# Sheet1.net
KiCad netlist of a schematic drawn in Altium Designer
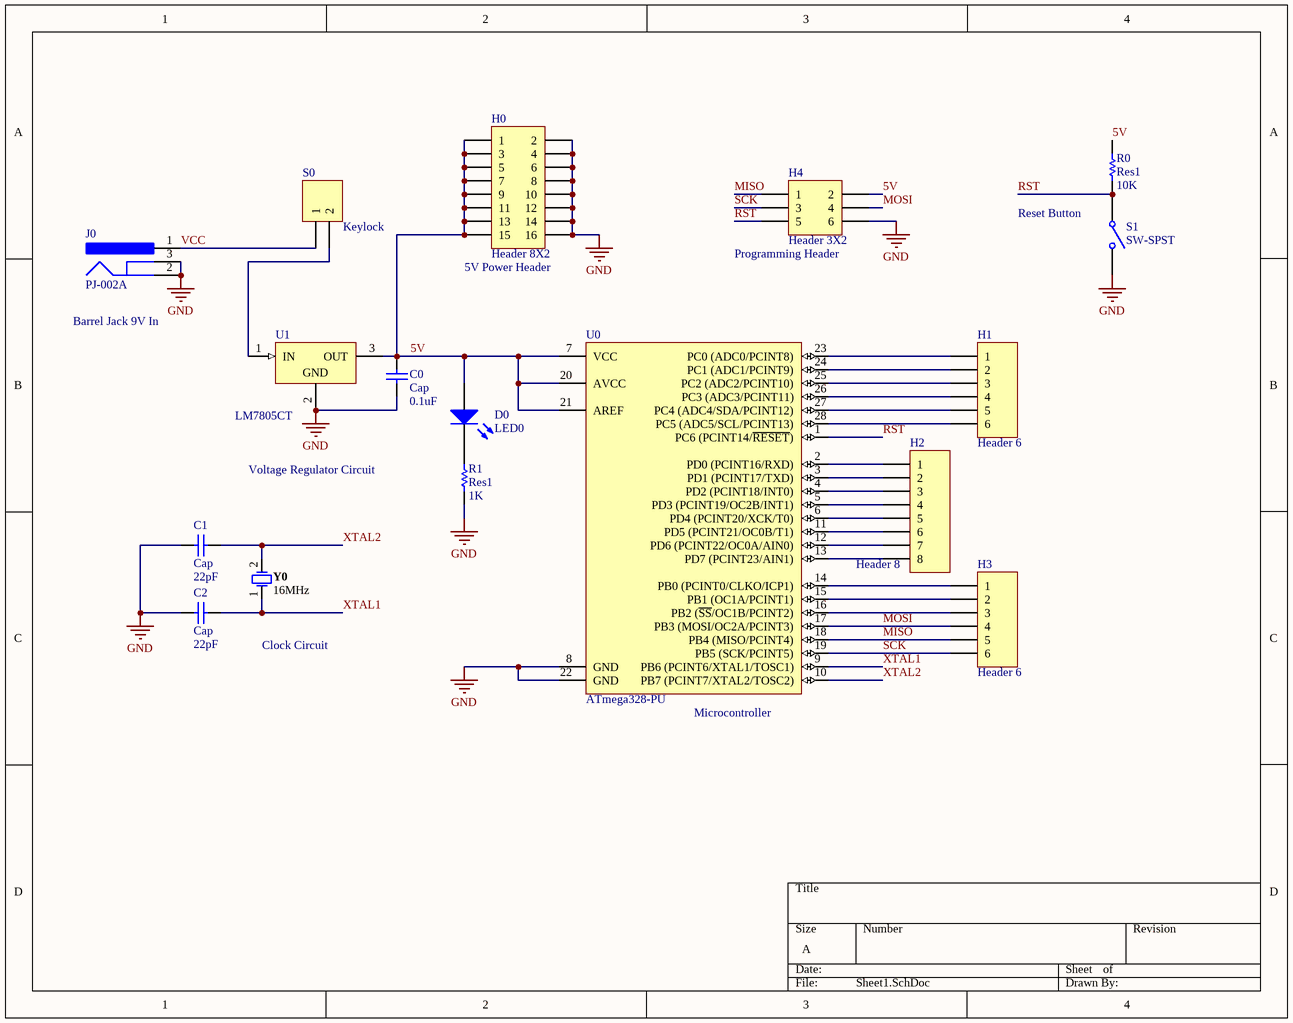
[diagram p0: Sheet1.SchDoc]

(export (version "E")
  (design (tool "Eeschema 10.0.6"))
  (components
    (comp (ref "C0")
      (value "Cap")
      (footprint "RAD-0.3")
      (description "Capacitor")
      (fields (field (name "ALTIUM_VALUE") "0.1uF") (field (name "PUBLISHER") "Altium Limited"))
      (libsource (lib "Miscellaneous Devices") (part "Cap"))
    )
    (comp (ref "C1")
      (value "Cap")
      (footprint "RAD-0.3")
      (description "Capacitor")
      (fields (field (name "ALTIUM_VALUE") "22pF") (field (name "PUBLISHER") "Altium Limited"))
      (libsource (lib "Miscellaneous Devices") (part "Cap"))
    )
    (comp (ref "C2")
      (value "Cap")
      (footprint "RAD-0.3")
      (description "Capacitor")
      (fields (field (name "ALTIUM_VALUE") "22pF") (field (name "PUBLISHER") "Altium Limited"))
      (libsource (lib "Miscellaneous Devices") (part "Cap"))
    )
    (comp (ref "D0")
      (value "LED0")
      (footprint "LED-0")
      (description "Typical INFRARED GaAs LED")
      (fields (field (name "PUBLISHER") "Altium Limited"))
      (libsource (lib "Miscellaneous Devices") (part "LED0"))
    )
    (comp (ref "H0")
      (value "Header 8X2")
      (footprint "HDR2X8")
      (description "Header, 8-Pin, Dual row")
      (fields (field (name "PUBLISHER") "Altium Limited"))
      (libsource (lib "Miscellaneous Connectors") (part "Header 8X2"))
    )
    (comp (ref "H1")
      (value "Header 6")
      (footprint "HDR1X6")
      (description "Header, 6-Pin")
      (fields (field (name "PUBLISHER") "Altium Limited"))
      (libsource (lib "Miscellaneous Connectors") (part "Header 6"))
    )
    (comp (ref "H2")
      (value "Header 8")
      (footprint "HDR1X8")
      (description "Header, 8-Pin")
      (fields (field (name "PUBLISHER") "Altium Limited"))
      (libsource (lib "Miscellaneous Connectors") (part "Header 8"))
    )
    (comp (ref "H3")
      (value "Header 6")
      (footprint "HDR1X6")
      (description "Header, 6-Pin")
      (fields (field (name "PUBLISHER") "Altium Limited"))
      (libsource (lib "Miscellaneous Connectors") (part "Header 6"))
    )
    (comp (ref "H4")
      (value "Header 3X2")
      (footprint "HDR2X3")
      (description "Header, 3-Pin, Dual row")
      (fields (field (name "PUBLISHER") "Altium Limited"))
      (libsource (lib "Miscellaneous Connectors") (part "Header 3X2"))
    )
    (comp (ref "J0")
      (value "PJ-002A")
      (footprint "CUI-PJ-002A_V")
      (fields (field (name "MANUFACTURER") "CUIInc."))
      (libsource (lib "Altium Content Vault") (part "JACK-2CD3-RN_B"))
    )
    (comp (ref "R0")
      (value "Res1")
      (footprint "AXIAL-0.5")
      (description "Resistor")
      (fields (field (name "ALTIUM_VALUE") "10K") (field (name "PUBLISHER") "Altium Limited"))
      (libsource (lib "Miscellaneous Devices") (part "Res1"))
    )
    (comp (ref "R1")
      (value "Res1")
      (footprint "AXIAL-0.5")
      (description "Resistor")
      (fields (field (name "ALTIUM_VALUE") "1K") (field (name "PUBLISHER") "Altium Limited"))
      (libsource (lib "Miscellaneous Devices") (part "Res1"))
    )
    (comp (ref "S0")
      (value "Keylock")
      (footprint "HDR1X2")
      (description "Header, 2-Pin")
      (fields (field (name "PUBLISHER") "Altium Limited"))
      (libsource (lib "Miscellaneous Connectors") (part "Header 2"))
    )
    (comp (ref "S1")
      (value "SW-SPST")
      (footprint "SPST-2")
      (description "Single-Pole, Single-Throw Switch")
      (fields (field (name "PUBLISHER") "Altium Limited"))
      (libsource (lib "Miscellaneous Devices") (part "SW-SPST"))
    )
    (comp (ref "U0")
      (value "ATmega328-PU")
      (footprint "28P3")
      (libsource (lib "Altium Content Vault") (part "MC-8B-ATM48-IL28"))
    )
    (comp (ref "U1")
      (value "LM7805CT")
      (footprint "FAIR-TO-220-3")
      (description "Positive Voltage Regulator, 5 V, 1 A, -40 to 125 degC, 3-Pin TO-220, RoHS, Tube")
      (fields (field (name "MANUFACTURER") "FairchildSemiconductor"))
      (libsource (lib "Altium Content Vault") (part "FAIR-LM7805CT-TO220-3"))
    )
    (comp (ref "Y0")
      (value "16MHz")
      (footprint "FOX-FOXSLF160-20")
      (description "Resistance Weld Thru-Hole Crystal, 16 MHz, -20 to 70 degC, 2-Pin THD, RoHS, Bulk")
      (fields (field (name "TOLERANCE") "1%"))
      (libsource (lib "Altium Content Vault") (part "XTAL-1-2-2"))
    )
  )
  (nets
    (net (code "1") (name "/5V") (class "Default")
      (node (ref "C0") (pin "2") (pinfunction "2_2") (pintype "passive"))
      (node (ref "D0") (pin "1") (pinfunction "A_1") (pintype "passive"))
      (node (ref "H0") (pin "1") (pinfunction "1_1") (pintype "passive"))
      (node (ref "H0") (pin "11") (pinfunction "11_11") (pintype "passive"))
      (node (ref "H0") (pin "13") (pinfunction "13_13") (pintype "passive"))
      (node (ref "H0") (pin "15") (pinfunction "15_15") (pintype "passive"))
      (node (ref "H0") (pin "3") (pinfunction "3_3") (pintype "passive"))
      (node (ref "H0") (pin "5") (pinfunction "5_5") (pintype "passive"))
      (node (ref "H0") (pin "7") (pinfunction "7_7") (pintype "passive"))
      (node (ref "H0") (pin "9") (pinfunction "9_9") (pintype "passive"))
      (node (ref "H4") (pin "2") (pinfunction "2_2") (pintype "passive"))
      (node (ref "R0") (pin "2") (pinfunction "2_2") (pintype "passive"))
      (node (ref "U0") (pin "20") (pinfunction "AVCC_20") (pintype "power_in"))
      (node (ref "U0") (pin "21") (pinfunction "AREF_21") (pintype "power_in"))
      (node (ref "U0") (pin "7") (pinfunction "VCC_7") (pintype "power_in"))
      (node (ref "U1") (pin "3") (pinfunction "OUT_3") (pintype "power_in"))
    )
    (net (code "2") (name "/MISO") (class "Default")
      (node (ref "H3") (pin "5") (pinfunction "5_5") (pintype "passive"))
      (node (ref "H4") (pin "1") (pinfunction "1_1") (pintype "passive"))
      (node (ref "U0") (pin "18") (pinfunction "PB4_(MISO/PCINT4)_18") (pintype "bidirectional"))
    )
    (net (code "3") (name "/MOSI") (class "Default")
      (node (ref "H3") (pin "4") (pinfunction "4_4") (pintype "passive"))
      (node (ref "H4") (pin "4") (pinfunction "4_4") (pintype "passive"))
      (node (ref "U0") (pin "17") (pinfunction "PB3_(MOSI/OC2A/PCINT3)_17") (pintype "bidirectional"))
    )
    (net (code "4") (name "/RST") (class "Default")
      (node (ref "H4") (pin "5") (pinfunction "5_5") (pintype "passive"))
      (node (ref "R0") (pin "1") (pinfunction "1_1") (pintype "passive"))
      (node (ref "S1") (pin "1") (pinfunction "COMMON_1") (pintype "passive"))
      (node (ref "U0") (pin "1") (pinfunction "PC6_(PCINT14/~{RESET})_1") (pintype "bidirectional"))
    )
    (net (code "5") (name "/SCK") (class "Default")
      (node (ref "H3") (pin "6") (pinfunction "6_6") (pintype "passive"))
      (node (ref "H4") (pin "3") (pinfunction "3_3") (pintype "passive"))
      (node (ref "U0") (pin "19") (pinfunction "PB5_(SCK/PCINT5)_19") (pintype "bidirectional"))
    )
    (net (code "6") (name "/VCC") (class "Default")
      (node (ref "J0") (pin "1") (pinfunction "1_1") (pintype "passive"))
      (node (ref "S0") (pin "1") (pinfunction "1_1") (pintype "passive"))
    )
    (net (code "7") (name "/XTAL1") (class "Default")
      (node (ref "C2") (pin "2") (pinfunction "2_2") (pintype "passive"))
      (node (ref "U0") (pin "9") (pinfunction "PB6_(PCINT6/XTAL1/TOSC1)_9") (pintype "bidirectional"))
      (node (ref "Y0") (pin "1") (pinfunction "1_1") (pintype "passive"))
    )
    (net (code "8") (name "/XTAL2") (class "Default")
      (node (ref "C1") (pin "2") (pinfunction "2_2") (pintype "passive"))
      (node (ref "U0") (pin "10") (pinfunction "PB7_(PCINT7/XTAL2/TOSC2)_10") (pintype "bidirectional"))
      (node (ref "Y0") (pin "2") (pinfunction "2_2") (pintype "passive"))
    )
    (net (code "9") (name "GND") (class "Default")
      (node (ref "C0") (pin "1") (pinfunction "1_1") (pintype "passive"))
      (node (ref "C1") (pin "1") (pinfunction "1_1") (pintype "passive"))
      (node (ref "C2") (pin "1") (pinfunction "1_1") (pintype "passive"))
      (node (ref "H0") (pin "10") (pinfunction "10_10") (pintype "passive"))
      (node (ref "H0") (pin "12") (pinfunction "12_12") (pintype "passive"))
      (node (ref "H0") (pin "14") (pinfunction "14_14") (pintype "passive"))
      (node (ref "H0") (pin "16") (pinfunction "16_16") (pintype "passive"))
      (node (ref "H0") (pin "2") (pinfunction "2_2") (pintype "passive"))
      (node (ref "H0") (pin "4") (pinfunction "4_4") (pintype "passive"))
      (node (ref "H0") (pin "6") (pinfunction "6_6") (pintype "passive"))
      (node (ref "H0") (pin "8") (pinfunction "8_8") (pintype "passive"))
      (node (ref "H4") (pin "6") (pinfunction "6_6") (pintype "passive"))
      (node (ref "J0") (pin "2") (pinfunction "2_2") (pintype "passive"))
      (node (ref "J0") (pin "3") (pinfunction "3_3") (pintype "passive"))
      (node (ref "R1") (pin "1") (pinfunction "1_1") (pintype "passive"))
      (node (ref "S1") (pin "2") (pinfunction "NO_2") (pintype "passive"))
      (node (ref "U0") (pin "22") (pinfunction "GND_22") (pintype "power_in"))
      (node (ref "U0") (pin "8") (pinfunction "GND_8") (pintype "power_in"))
      (node (ref "U1") (pin "2") (pinfunction "GND_2") (pintype "passive"))
    )
    (net (code "10") (name "Net-(D0-K)") (class "Default")
      (node (ref "D0") (pin "2") (pinfunction "K_2") (pintype "passive"))
      (node (ref "R1") (pin "2") (pinfunction "2_2") (pintype "passive"))
    )
    (net (code "11") (name "Net-(U0-PB0_(PCINT0{slash}CLKO{slash}ICP1))") (class "Default")
      (node (ref "H3") (pin "1") (pinfunction "1_1") (pintype "passive"))
      (node (ref "U0") (pin "14") (pinfunction "PB0_(PCINT0/CLKO/ICP1)_14") (pintype "bidirectional"))
    )
    (net (code "12") (name "Net-(U0-PB1_(OC1A{slash}PCINT1))") (class "Default")
      (node (ref "H3") (pin "2") (pinfunction "2_2") (pintype "passive"))
      (node (ref "U0") (pin "15") (pinfunction "PB1_(OC1A/PCINT1)_15") (pintype "bidirectional"))
    )
    (net (code "13") (name "Net-(U0-PB2_(~{SS}{slash}OC1B{slash}PCINT2))") (class "Default")
      (node (ref "H3") (pin "3") (pinfunction "3_3") (pintype "passive"))
      (node (ref "U0") (pin "16") (pinfunction "PB2_(~{SS}/OC1B/PCINT2)_16") (pintype "bidirectional"))
    )
    (net (code "14") (name "Net-(U0-PC0_(ADC0{slash}PCINT8))") (class "Default")
      (node (ref "H1") (pin "1") (pinfunction "1_1") (pintype "passive"))
      (node (ref "U0") (pin "23") (pinfunction "PC0_(ADC0/PCINT8)_23") (pintype "bidirectional"))
    )
    (net (code "15") (name "Net-(U0-PC1_(ADC1{slash}PCINT9))") (class "Default")
      (node (ref "H1") (pin "2") (pinfunction "2_2") (pintype "passive"))
      (node (ref "U0") (pin "24") (pinfunction "PC1_(ADC1/PCINT9)_24") (pintype "bidirectional"))
    )
    (net (code "16") (name "Net-(U0-PC2_(ADC2{slash}PCINT10))") (class "Default")
      (node (ref "H1") (pin "3") (pinfunction "3_3") (pintype "passive"))
      (node (ref "U0") (pin "25") (pinfunction "PC2_(ADC2/PCINT10)_25") (pintype "bidirectional"))
    )
    (net (code "17") (name "Net-(U0-PC3_(ADC3{slash}PCINT11))") (class "Default")
      (node (ref "H1") (pin "4") (pinfunction "4_4") (pintype "passive"))
      (node (ref "U0") (pin "26") (pinfunction "PC3_(ADC3/PCINT11)_26") (pintype "bidirectional"))
    )
    (net (code "18") (name "Net-(U0-PC4_(ADC4{slash}SDA{slash}PCINT12))") (class "Default")
      (node (ref "H1") (pin "5") (pinfunction "5_5") (pintype "passive"))
      (node (ref "U0") (pin "27") (pinfunction "PC4_(ADC4/SDA/PCINT12)_27") (pintype "bidirectional"))
    )
    (net (code "19") (name "Net-(U0-PC5_(ADC5{slash}SCL{slash}PCINT13))") (class "Default")
      (node (ref "H1") (pin "6") (pinfunction "6_6") (pintype "passive"))
      (node (ref "U0") (pin "28") (pinfunction "PC5_(ADC5/SCL/PCINT13)_28") (pintype "bidirectional"))
    )
    (net (code "20") (name "Net-(U0-PD0_(PCINT16{slash}RXD))") (class "Default")
      (node (ref "H2") (pin "1") (pinfunction "1_1") (pintype "passive"))
      (node (ref "U0") (pin "2") (pinfunction "PD0_(PCINT16/RXD)_2") (pintype "bidirectional"))
    )
    (net (code "21") (name "Net-(U0-PD1_(PCINT17{slash}TXD))") (class "Default")
      (node (ref "H2") (pin "2") (pinfunction "2_2") (pintype "passive"))
      (node (ref "U0") (pin "3") (pinfunction "PD1_(PCINT17/TXD)_3") (pintype "bidirectional"))
    )
    (net (code "22") (name "Net-(U0-PD2_(PCINT18{slash}INT0))") (class "Default")
      (node (ref "H2") (pin "3") (pinfunction "3_3") (pintype "passive"))
      (node (ref "U0") (pin "4") (pinfunction "PD2_(PCINT18/INT0)_4") (pintype "bidirectional"))
    )
    (net (code "23") (name "Net-(U0-PD3_(PCINT19{slash}OC2B{slash}INT1))") (class "Default")
      (node (ref "H2") (pin "4") (pinfunction "4_4") (pintype "passive"))
      (node (ref "U0") (pin "5") (pinfunction "PD3_(PCINT19/OC2B/INT1)_5") (pintype "bidirectional"))
    )
    (net (code "24") (name "Net-(U0-PD4_(PCINT20{slash}XCK{slash}T0))") (class "Default")
      (node (ref "H2") (pin "5") (pinfunction "5_5") (pintype "passive"))
      (node (ref "U0") (pin "6") (pinfunction "PD4_(PCINT20/XCK/T0)_6") (pintype "bidirectional"))
    )
    (net (code "25") (name "Net-(U0-PD5_(PCINT21{slash}OC0B{slash}T1))") (class "Default")
      (node (ref "H2") (pin "6") (pinfunction "6_6") (pintype "passive"))
      (node (ref "U0") (pin "11") (pinfunction "PD5_(PCINT21/OC0B/T1)_11") (pintype "bidirectional"))
    )
    (net (code "26") (name "Net-(U0-PD6_(PCINT22{slash}OC0A{slash}AIN0))") (class "Default")
      (node (ref "H2") (pin "7") (pinfunction "7_7") (pintype "passive"))
      (node (ref "U0") (pin "12") (pinfunction "PD6_(PCINT22/OC0A/AIN0)_12") (pintype "bidirectional"))
    )
    (net (code "27") (name "Net-(U0-PD7_(PCINT23{slash}AIN1))") (class "Default")
      (node (ref "H2") (pin "8") (pinfunction "8_8") (pintype "passive"))
      (node (ref "U0") (pin "13") (pinfunction "PD7_(PCINT23/AIN1)_13") (pintype "bidirectional"))
    )
    (net (code "28") (name "Net-(U1-IN)") (class "Default")
      (node (ref "S0") (pin "2") (pinfunction "2_2") (pintype "power_in"))
      (node (ref "U1") (pin "1") (pinfunction "IN_1") (pintype "input"))
    )
  )
)
